# MCU.net
KiCad netlist of a schematic drawn in Altium Designer
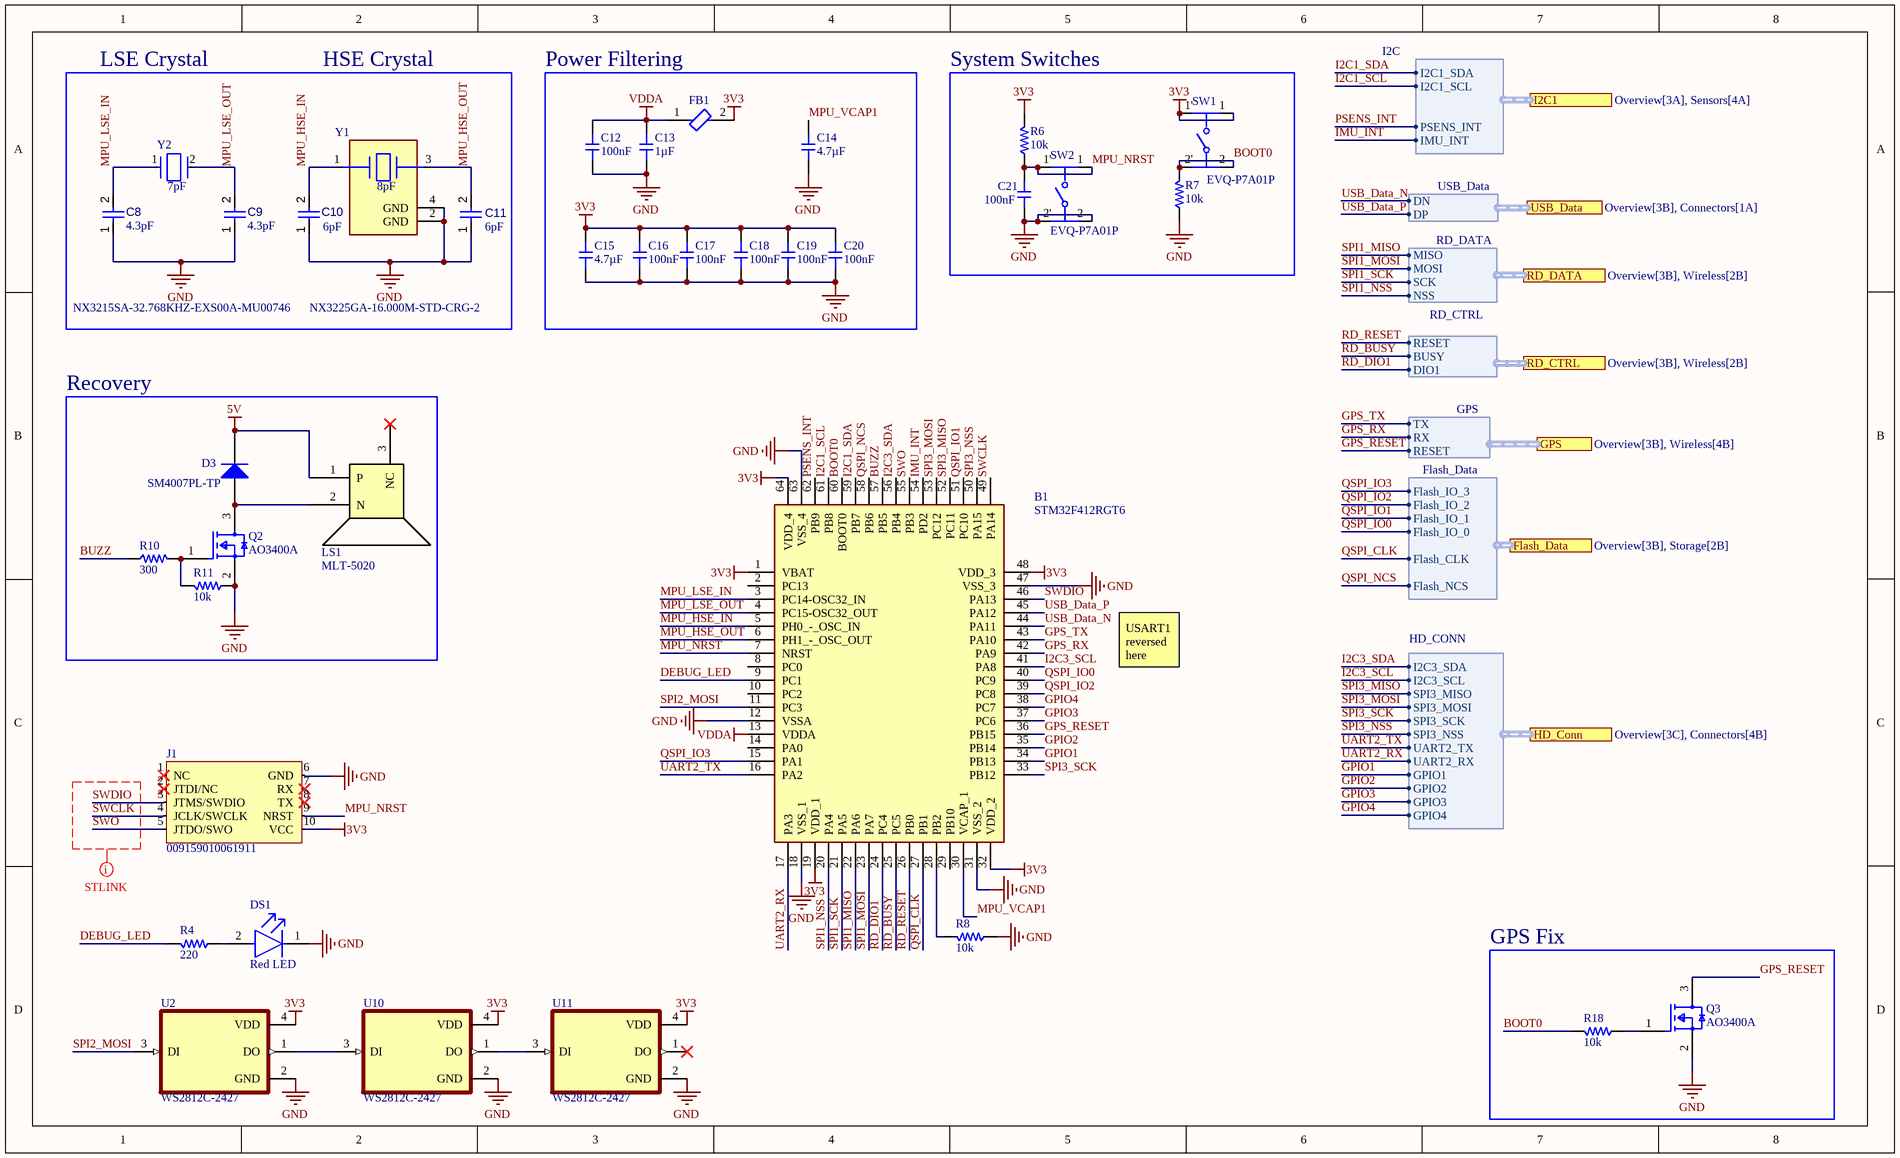
[diagram p0: MCU.SchDoc]

(export (version "E")
  (design (tool "Eeschema 10.0.6"))
  (components
    (comp (ref "B1")
      (value "STM32F412RGT6")
      (footprint "QFP50P1200X1200X160-64N")
      (description "ARM Microcontrollers - MCU 16/32-BITS MICROS")
      (fields
        (field (name "MANUFACTURER") "STMicroelectronics")
        (field (name "MOUSER PART NUMBER") "511-STM32F412RGT6")
      )
      (libsource (lib "StrathSEDS") (part "STM32F412RGT6"))
    )
    (comp (ref "C8")
      (value "4.3pF")
      (footprint "CAP-0402")
      (description "50V 4.3pF NP0 0402  Multilayer Ceramic Capacitors MLCC - SMD/SMT ROHS")
      (fields (field (name "JLCPCB PART NUMBER") "C147367") (field (name "Comment") "C1005NP0439CGTS"))
      (libsource (lib "StrathSEDS") (part "CAP-NP-2"))
    )
    (comp (ref "C9")
      (value "4.3pF")
      (footprint "CAP-0402")
      (description "50V 4.3pF NP0 0402  Multilayer Ceramic Capacitors MLCC - SMD/SMT ROHS")
      (fields (field (name "JLCPCB PART NUMBER") "C147367") (field (name "Comment") "C1005NP0439CGTS"))
      (libsource (lib "StrathSEDS") (part "CAP-NP-2"))
    )
    (comp (ref "C10")
      (value "6pF")
      (footprint "CAP-0402")
      (description "50V 6pF C0G 0402  Multilayer Ceramic Capacitors MLCC - SMD/SMT ROHS")
      (fields (field (name "JLCPCB PART NUMBER") "C1575") (field (name "Comment") "0402CG6R0C500NT"))
      (libsource (lib "StrathSEDS") (part "CAP-NP-2"))
    )
    (comp (ref "C11")
      (value "6pF")
      (footprint "CAP-0402")
      (description "50V 6pF C0G 0402  Multilayer Ceramic Capacitors MLCC - SMD/SMT ROHS")
      (fields (field (name "JLCPCB PART NUMBER") "C1575") (field (name "Comment") "0402CG6R0C500NT"))
      (libsource (lib "StrathSEDS") (part "CAP-NP-2"))
    )
    (comp (ref "C12")
      (value "100nF")
      (footprint "CAP-0402")
      (description "Capacitor, Ceramic (MLCC), 100nF, ±10%, 16V, X7R, ±10%, SMD 0402")
      (fields (field (name "TOLERANCE") "10%") (field (name "JLCPCB BASIC PART") "Yes"))
      (libsource (lib "StrathSEDS") (part "GRM21BR61H106KE43L"))
    )
    (comp (ref "C13")
      (value "1µF")
      (footprint "CAP-0402")
      (description "Capacitor, Ceramic (MLCC), 1uF, ±10%, 25V, X5R, ±10%, SMD 0402")
      (fields (field (name "TOLERANCE") "10%") (field (name "JLCPCB BASIC PART") "Yes"))
      (libsource (lib "StrathSEDS") (part "GRM21BR61H106KE43L"))
    )
    (comp (ref "C14")
      (value "4.7µF")
      (footprint "CAP-0402")
      (description "Capacitor, Ceramic (MLCC), 4.7uF, ±20%, 10V, X5R, ±20%, SMD 0402")
      (fields (field (name "TOLERANCE") "20%") (field (name "MANUFACTURER PART NUMBER") "CL05A475MP5NRNC"))
      (libsource (lib "StrathSEDS") (part "GRM21BR61H106KE43L"))
    )
    (comp (ref "C15")
      (value "4.7µF")
      (footprint "CAP-0402")
      (description "Capacitor, Ceramic (MLCC), 4.7uF, ±20%, 10V, X5R, ±20%, SMD 0402")
      (fields (field (name "TOLERANCE") "20%") (field (name "MANUFACTURER PART NUMBER") "CL05A475MP5NRNC"))
      (libsource (lib "StrathSEDS") (part "GRM21BR61H106KE43L"))
    )
    (comp (ref "C16")
      (value "100nF")
      (footprint "CAP-0402")
      (description "Capacitor, Ceramic (MLCC), 100nF, ±10%, 16V, X7R, ±10%, SMD 0402")
      (fields (field (name "TOLERANCE") "10%") (field (name "JLCPCB BASIC PART") "Yes"))
      (libsource (lib "StrathSEDS") (part "GRM21BR61H106KE43L"))
    )
    (comp (ref "C17")
      (value "100nF")
      (footprint "CAP-0402")
      (description "Capacitor, Ceramic (MLCC), 100nF, ±10%, 16V, X7R, ±10%, SMD 0402")
      (fields (field (name "TOLERANCE") "10%") (field (name "JLCPCB BASIC PART") "Yes"))
      (libsource (lib "StrathSEDS") (part "GRM21BR61H106KE43L"))
    )
    (comp (ref "C18")
      (value "100nF")
      (footprint "CAP-0402")
      (description "Capacitor, Ceramic (MLCC), 100nF, ±10%, 16V, X7R, ±10%, SMD 0402")
      (fields (field (name "TOLERANCE") "10%") (field (name "JLCPCB BASIC PART") "Yes"))
      (libsource (lib "StrathSEDS") (part "GRM21BR61H106KE43L"))
    )
    (comp (ref "C19")
      (value "100nF")
      (footprint "CAP-0402")
      (description "Capacitor, Ceramic (MLCC), 100nF, ±10%, 16V, X7R, ±10%, SMD 0402")
      (fields (field (name "TOLERANCE") "10%") (field (name "JLCPCB BASIC PART") "Yes"))
      (libsource (lib "StrathSEDS") (part "GRM21BR61H106KE43L"))
    )
    (comp (ref "C20")
      (value "100nF")
      (footprint "CAP-0402")
      (description "Capacitor, Ceramic (MLCC), 100nF, ±10%, 16V, X7R, ±10%, SMD 0402")
      (fields (field (name "TOLERANCE") "10%") (field (name "JLCPCB BASIC PART") "Yes"))
      (libsource (lib "StrathSEDS") (part "GRM21BR61H106KE43L"))
    )
    (comp (ref "C21")
      (value "100nF")
      (footprint "CAP-0402")
      (description "Capacitor, Ceramic (MLCC), 100nF, ±10%, 16V, X7R, ±10%, SMD 0402")
      (fields (field (name "TOLERANCE") "10%") (field (name "JLCPCB BASIC PART") "Yes"))
      (libsource (lib "StrathSEDS") (part "GRM21BR61H106KE43L"))
    )
    (comp (ref "D3")
      (value "SM4007PL-TP")
      (footprint "MCC-SOD-123FL_V")
      (description "DIODE GEN PURP 1KV 1A SOD123FL")
      (fields (field (name "LCSC PART #") "C64898"))
      (libsource (lib "StrathSEDS") (part "D-AK-2"))
    )
    (comp (ref "DS1")
      (value "Red LED")
      (footprint "FP-LTST-C190GKT-MFG")
      (description "SZYY0603R")
      (fields (field (name "JLCPCB PART NUMBER") "C2286"))
      (libsource (lib "StrathSEDS Mach 22") (part "8706943c75ba83719d021d2fdc84c58"))
    )
    (comp (ref "FB1")
      (value "BLM15AG601SN1D")
      (footprint "FP-BLM15-0_05-IPC_A")
      (description "520mΩ ±25% 600Ω@100MHz 0402  Ferrite Beads ROHS")
      (fields (field (name "JLCPCB PART NUMBER") "C76884"))
      (libsource (lib "StrathSEDS") (part "5f30dd21d616792df468990f7003faa"))
    )
    (comp (ref "J1")
      (value "009159010061911")
      (footprint "009159010061911-Footprint-1")
      (description "AVX edge to edge connector 10pin")
      (libsource (lib "StrathSEDS") (part "009159010061911"))
    )
    (comp (ref "LS1")
      (value "MLT-5020")
      (footprint "MLT-5020")
      (description "Externally Driven Magnetic 4000Hz SMD,5x5mm  Buzzers ROHS")
      (fields (field (name "JLCPCB PART NUMBER") "C94598"))
      (libsource (lib "StrathSEDS") (part "MLT-5020"))
    )
    (comp (ref "Q2")
      (value "AO3400A")
      (footprint "FP-SOT23-IPC_C")
      (description "N沟道 VDS=30V VGS=±12V ID=5.7A P=1.4W")
      (fields (field (name "LCSC PART #") "C20917"))
      (libsource (lib "StrathSEDS") (part "0a9ea7c96deaaede766a5b531c28de0"))
    )
    (comp (ref "Q3")
      (value "AO3400A")
      (footprint "FP-SOT23-IPC_C")
      (description "N沟道 VDS=30V VGS=±12V ID=5.7A P=1.4W")
      (fields (field (name "JLCPCB PART NUMBER") "C20917"))
      (libsource (lib "StrathSEDS") (part "0a9ea7c96deaaede766a5b531c28de0"))
    )
    (comp (ref "R4")
      (value "220")
      (footprint "RES-0402")
      (description "Resistor, 220Ω, ±1%, 62.5mW, 50V, ±100ppm/℃, -55℃~+155℃, SMD 0402")
      (fields (field (name "MANUFACTURER") "Uniroyal") (field (name "TOLERANCE") "1%"))
      (libsource (lib "StrathSEDS") (part "1206W4F7500T5E"))
    )
    (comp (ref "R6")
      (value "10k")
      (footprint "RES-0402")
      (description "Resistor, 10kΩ, ±1%, 62.5mW, 50V, ±100ppm/℃, -55℃~+155℃, SMD 0402")
      (fields (field (name "TOLERANCE") "1%") (field (name "JLCPCB PART NUMBER") "C25744"))
      (libsource (lib "StrathSEDS") (part "1206W4F7500T5E"))
    )
    (comp (ref "R7")
      (value "10k")
      (footprint "RES-0402")
      (description "Resistor, 10kΩ, ±1%, 62.5mW, 50V, ±100ppm/℃, -55℃~+155℃, SMD 0402")
      (fields (field (name "TOLERANCE") "1%") (field (name "JLCPCB PART NUMBER") "C25744"))
      (libsource (lib "StrathSEDS") (part "1206W4F7500T5E"))
    )
    (comp (ref "R8")
      (value "10k")
      (footprint "RES-0402")
      (description "Resistor, 10kΩ, ±1%, 62.5mW, 50V, ±100ppm/℃, -55℃~+155℃, SMD 0402")
      (fields (field (name "TOLERANCE") "1%") (field (name "JLCPCB PART NUMBER") "C25744"))
      (libsource (lib "StrathSEDS") (part "1206W4F7500T5E"))
    )
    (comp (ref "R10")
      (value "300")
      (footprint "RES-0402")
      (description "Resistor, 300Ω, ±1%, 62.5mW, 50V, ±100ppm/℃, -55℃~+155℃, SMD 0402")
      (fields
        (field (name "JLCPCB PART NUMBER") "C25102")
        (field (name "MANUFACTURER PART NUMBER") "0402WGF3000TCE")
      )
      (libsource (lib "StrathSEDS") (part "1206W4F7500T5E"))
    )
    (comp (ref "R11")
      (value "10k")
      (footprint "RES-0402")
      (description "Resistor, 10kΩ, ±1%, 62.5mW, 50V, ±100ppm/℃, -55℃~+155℃, SMD 0402")
      (fields (field (name "TOLERANCE") "1%") (field (name "JLCPCB PART NUMBER") "C25744"))
      (libsource (lib "StrathSEDS") (part "1206W4F7500T5E"))
    )
    (comp (ref "R18")
      (value "10k")
      (footprint "RES-0402")
      (description "Resistor, 10kΩ, ±1%, 62.5mW, 50V, ±100ppm/℃, -55℃~+155℃, SMD 0402")
      (fields (field (name "TOLERANCE") "1%") (field (name "JLCPCB PART NUMBER") "C25744"))
      (libsource (lib "StrathSEDS") (part "1206W4F7500T5E"))
    )
    (comp (ref "SW1")
      (value "EVQ-P7A01P")
      (footprint "FP-EVQ-P7A01P-MFG")
      (description "Switch Tactile N.O. SPST Rectangular Button Gull Wing 0.05A 12VDC 2.2N SMD Embossed T/R")
      (fields (field (name "JLCPCB PART NUMBER") "C79167"))
      (libsource (lib "StrathSEDS") (part "c93661f14280f1e5a1fd29b4a471f7d"))
    )
    (comp (ref "SW2")
      (value "EVQ-P7A01P")
      (footprint "FP-EVQ-P7A01P-MFG")
      (description "Switch Tactile N.O. SPST Rectangular Button Gull Wing 0.05A 12VDC 2.2N SMD Embossed T/R")
      (fields (field (name "JLCPCB PART NUMBER") "C79167"))
      (libsource (lib "StrathSEDS") (part "c93661f14280f1e5a1fd29b4a471f7d"))
    )
    (comp (ref "U2")
      (value "WS2812C-2427")
      (footprint "WS2812C-2427-Footprint-1")
      (description "SMD,2.4x2.7mm  Light Emitting Diodes (LED) ROHS")
      (fields (field (name "JLCPCB PART NUMBER") "C4154872"))
      (libsource (lib "StrathSEDS") (part "WS2812C-2427"))
    )
    (comp (ref "U10")
      (value "WS2812C-2427")
      (footprint "WS2812C-2427-Footprint-1")
      (description "SMD,2.4x2.7mm  Light Emitting Diodes (LED) ROHS")
      (fields (field (name "JLCPCB PART NUMBER") "C4154872"))
      (libsource (lib "StrathSEDS") (part "WS2812C-2427"))
    )
    (comp (ref "U11")
      (value "WS2812C-2427")
      (footprint "WS2812C-2427-Footprint-1")
      (description "SMD,2.4x2.7mm  Light Emitting Diodes (LED) ROHS")
      (fields (field (name "JLCPCB PART NUMBER") "C4154872"))
      (libsource (lib "StrathSEDS") (part "WS2812C-2427"))
    )
    (comp (ref "Y1")
      (value "NX3225GA-16.000M-STD-CRG-2")
      (footprint "FP-NX3225GA-MFG")
      (description "Crystal 16MHz ±20ppm (Tol) ±30ppm (Stability) 8pF FUND 80Ohm Automotive 4-Pin SMD")
      (fields (field (name "JLCPCB PART NUMBER") "C156247") (field (name "ALTIUM_VALUE") "8pF"))
      (libsource (lib "StrathSEDS Mach 22") (part "6320effb7d3e443b36bf79d8ebe02e5"))
    )
    (comp (ref "Y2")
      (value "NX3215SA-32.768KHZ-EXS00A-MU00746")
      (footprint "FP-NX3215SA-MFG")
      (description "Crystal 32.7680KHZ 7PF SMD")
      (fields (field (name "JLCPCB PART NUMBER") "C5136773") (field (name "ALTIUM_VALUE") "7pF"))
      (libsource (lib "StrathSEDS Mach 22") (part "c23a69dc6c9e2f18f2079038eb95dd1"))
    )
  )
  (nets
    (net (code "8") (name "/BOOT0") (class "Default")
      (node (ref "B1") (pin "60") (pinfunction "BOOT0_60") (pintype "passive"))
      (node (ref "R18") (pin "2") (pinfunction "2_2") (pintype "passive"))
      (node (ref "R7") (pin "2") (pinfunction "2_2") (pintype "passive"))
      (node (ref "SW1") (pin "2") (pinfunction "2_2") (pintype "passive"))
      (node (ref "SW1") (pin "2'") (pinfunction "2'_2'") (pintype "passive"))
    )
    (net (code "9") (name "/BUZZ") (class "Default")
      (node (ref "B1") (pin "57") (pinfunction "PB5_57") (pintype "passive"))
      (node (ref "R10") (pin "1") (pinfunction "1_1") (pintype "passive"))
    )
    (net (code "10") (name "/DEBUG_LED") (class "Default")
      (node (ref "B1") (pin "9") (pinfunction "PC1_9") (pintype "passive"))
      (node (ref "R4") (pin "2") (pinfunction "2_2") (pintype "passive"))
    )
    (net (code "11") (name "/GPIO1") (class "Default")
      (node (ref "B1") (pin "34") (pinfunction "PB13_34") (pintype "passive"))
    )
    (net (code "12") (name "/GPIO2") (class "Default")
      (node (ref "B1") (pin "35") (pinfunction "PB14_35") (pintype "passive"))
    )
    (net (code "13") (name "/GPIO3") (class "Default")
      (node (ref "B1") (pin "37") (pinfunction "PC6_37") (pintype "passive"))
    )
    (net (code "14") (name "/GPIO4") (class "Default")
      (node (ref "B1") (pin "38") (pinfunction "PC7_38") (pintype "passive"))
    )
    (net (code "15") (name "/GPS_RESET") (class "Default")
      (node (ref "B1") (pin "36") (pinfunction "PB15_36") (pintype "passive"))
      (node (ref "Q3") (pin "3") (pinfunction "D_3") (pintype "passive"))
    )
    (net (code "16") (name "/GPS_RX") (class "Default")
      (node (ref "B1") (pin "42") (pinfunction "PA9_42") (pintype "passive"))
    )
    (net (code "17") (name "/GPS_TX") (class "Default")
      (node (ref "B1") (pin "43") (pinfunction "PA10_43") (pintype "passive"))
    )
    (net (code "18") (name "/I2C1_SCL") (class "Default")
      (node (ref "B1") (pin "61") (pinfunction "PB8_61") (pintype "passive"))
    )
    (net (code "19") (name "/I2C1_SDA") (class "Default")
      (node (ref "B1") (pin "59") (pinfunction "PB7_59") (pintype "passive"))
    )
    (net (code "20") (name "/I2C3_SCL") (class "Default")
      (node (ref "B1") (pin "41") (pinfunction "PA8_41") (pintype "passive"))
    )
    (net (code "21") (name "/I2C3_SDA") (class "Default")
      (node (ref "B1") (pin "56") (pinfunction "PB4_56") (pintype "passive"))
    )
    (net (code "22") (name "/IMU_INT") (class "Default")
      (node (ref "B1") (pin "54") (pinfunction "PD2_54") (pintype "passive"))
    )
    (net (code "23") (name "/MPU_HSE_IN") (class "Default")
      (node (ref "B1") (pin "5") (pinfunction "PH0_-_OSC_IN_5") (pintype "passive"))
      (node (ref "C10") (pin "2") (pinfunction "2_2") (pintype "passive"))
      (node (ref "Y1") (pin "1") (pinfunction "1_1") (pintype "passive"))
    )
    (net (code "24") (name "/MPU_HSE_OUT") (class "Default")
      (node (ref "B1") (pin "6") (pinfunction "PH1_-_OSC_OUT_6") (pintype "passive"))
      (node (ref "C11") (pin "2") (pinfunction "2_2") (pintype "passive"))
      (node (ref "Y1") (pin "3") (pinfunction "3_3") (pintype "passive"))
    )
    (net (code "25") (name "/MPU_LSE_IN") (class "Default")
      (node (ref "B1") (pin "3") (pinfunction "PC14-OSC32_IN_3") (pintype "passive"))
      (node (ref "C8") (pin "2") (pinfunction "2_2") (pintype "passive"))
      (node (ref "Y2") (pin "1") (pinfunction "1_1") (pintype "passive"))
    )
    (net (code "26") (name "/MPU_LSE_OUT") (class "Default")
      (node (ref "B1") (pin "4") (pinfunction "PC15-OSC32_OUT_4") (pintype "passive"))
      (node (ref "C9") (pin "2") (pinfunction "2_2") (pintype "passive"))
      (node (ref "Y2") (pin "2") (pinfunction "2_2") (pintype "passive"))
    )
    (net (code "27") (name "/MPU_NRST") (class "Default")
      (node (ref "B1") (pin "7") (pinfunction "NRST_7") (pintype "passive"))
      (node (ref "C21") (pin "2") (pinfunction "2_2") (pintype "passive"))
      (node (ref "J1") (pin "9") (pinfunction "NRST_9") (pintype "output"))
      (node (ref "R6") (pin "1") (pinfunction "1_1") (pintype "passive"))
      (node (ref "SW2") (pin "1") (pinfunction "1_1") (pintype "passive"))
      (node (ref "SW2") (pin "1'") (pinfunction "1'_1'") (pintype "passive"))
    )
    (net (code "28") (name "/MPU_VCAP1") (class "Default")
      (node (ref "B1") (pin "30") (pinfunction "VCAP_1_30") (pintype "power_in"))
      (node (ref "C14") (pin "2") (pinfunction "2_2") (pintype "passive"))
    )
    (net (code "29") (name "/PSENS_INT") (class "Default")
      (node (ref "B1") (pin "62") (pinfunction "PB9_62") (pintype "passive"))
    )
    (net (code "30") (name "/QSPI_CLK") (class "Default")
      (node (ref "B1") (pin "27") (pinfunction "PB1_27") (pintype "passive"))
    )
    (net (code "31") (name "/QSPI_IO0") (class "Default")
      (node (ref "B1") (pin "40") (pinfunction "PC9_40") (pintype "passive"))
    )
    (net (code "32") (name "/QSPI_IO1") (class "Default")
      (node (ref "B1") (pin "51") (pinfunction "PC10_51") (pintype "passive"))
    )
    (net (code "33") (name "/QSPI_IO2") (class "Default")
      (node (ref "B1") (pin "39") (pinfunction "PC8_39") (pintype "passive"))
    )
    (net (code "34") (name "/QSPI_IO3") (class "Default")
      (node (ref "B1") (pin "15") (pinfunction "PA1_15") (pintype "passive"))
    )
    (net (code "35") (name "/QSPI_NCS") (class "Default")
      (node (ref "B1") (pin "58") (pinfunction "PB6_58") (pintype "passive"))
    )
    (net (code "36") (name "/RD_BUSY") (class "Default")
      (node (ref "B1") (pin "25") (pinfunction "PC5_25") (pintype "passive"))
    )
    (net (code "37") (name "/RD_DIO1") (class "Default")
      (node (ref "B1") (pin "24") (pinfunction "PC4_24") (pintype "passive"))
    )
    (net (code "38") (name "/RD_RESET") (class "Default")
      (node (ref "B1") (pin "26") (pinfunction "PB0_26") (pintype "passive"))
    )
    (net (code "39") (name "/SPI1_MISO") (class "Default")
      (node (ref "B1") (pin "22") (pinfunction "PA6_22") (pintype "passive"))
    )
    (net (code "40") (name "/SPI1_MOSI") (class "Default")
      (node (ref "B1") (pin "23") (pinfunction "PA7_23") (pintype "passive"))
    )
    (net (code "41") (name "/SPI1_NSS") (class "Default")
      (node (ref "B1") (pin "20") (pinfunction "PA4_20") (pintype "passive"))
    )
    (net (code "42") (name "/SPI1_SCK") (class "Default")
      (node (ref "B1") (pin "21") (pinfunction "PA5_21") (pintype "passive"))
    )
    (net (code "43") (name "/SPI2_MOSI") (class "Default")
      (node (ref "B1") (pin "11") (pinfunction "PC3_11") (pintype "passive"))
      (node (ref "U2") (pin "3") (pinfunction "DI_3") (pintype "input"))
    )
    (net (code "44") (name "/SPI3_MISO") (class "Default")
      (node (ref "B1") (pin "52") (pinfunction "PC11_52") (pintype "passive"))
    )
    (net (code "45") (name "/SPI3_MOSI") (class "Default")
      (node (ref "B1") (pin "53") (pinfunction "PC12_53") (pintype "passive"))
    )
    (net (code "46") (name "/SPI3_NSS") (class "Default")
      (node (ref "B1") (pin "50") (pinfunction "PA15_50") (pintype "passive"))
    )
    (net (code "47") (name "/SPI3_SCK") (class "Default")
      (node (ref "B1") (pin "33") (pinfunction "PB12_33") (pintype "passive"))
    )
    (net (code "48") (name "/SWCLK") (class "Default")
      (node (ref "B1") (pin "49") (pinfunction "PA14_49") (pintype "passive"))
      (node (ref "J1") (pin "4") (pinfunction "JCLK/SWCLK_4") (pintype "output"))
    )
    (net (code "49") (name "/SWDIO") (class "Default")
      (node (ref "B1") (pin "46") (pinfunction "PA13_46") (pintype "passive"))
      (node (ref "J1") (pin "3") (pinfunction "JTMS/SWDIO_3") (pintype "bidirectional"))
    )
    (net (code "50") (name "/SWO") (class "Default")
      (node (ref "B1") (pin "55") (pinfunction "PB3_55") (pintype "passive"))
      (node (ref "J1") (pin "5") (pinfunction "JTDO/SWO_5") (pintype "input"))
    )
    (net (code "51") (name "/UART2_RX") (class "Default")
      (node (ref "B1") (pin "17") (pinfunction "PA3_17") (pintype "passive"))
    )
    (net (code "52") (name "/UART2_TX") (class "Default")
      (node (ref "B1") (pin "16") (pinfunction "PA2_16") (pintype "passive"))
    )
    (net (code "53") (name "/USB_Data_N") (class "Default")
      (node (ref "B1") (pin "44") (pinfunction "PA11_44") (pintype "passive"))
    )
    (net (code "54") (name "/USB_Data_P") (class "Default")
      (node (ref "B1") (pin "45") (pinfunction "PA12_45") (pintype "passive"))
    )
    (net (code "62") (name "3V3") (class "Default")
      (node (ref "B1") (pin "1") (pinfunction "VBAT_1") (pintype "power_in"))
      (node (ref "B1") (pin "19") (pinfunction "VDD_1_19") (pintype "power_in"))
      (node (ref "B1") (pin "32") (pinfunction "VDD_2_32") (pintype "power_in"))
      (node (ref "B1") (pin "48") (pinfunction "VDD_3_48") (pintype "power_in"))
      (node (ref "B1") (pin "64") (pinfunction "VDD_4_64") (pintype "power_in"))
      (node (ref "C15") (pin "2") (pinfunction "2_2") (pintype "passive"))
      (node (ref "C16") (pin "2") (pinfunction "2_2") (pintype "passive"))
      (node (ref "C17") (pin "2") (pinfunction "2_2") (pintype "passive"))
      (node (ref "C18") (pin "2") (pinfunction "2_2") (pintype "passive"))
      (node (ref "C19") (pin "2") (pinfunction "2_2") (pintype "passive"))
      (node (ref "C20") (pin "2") (pinfunction "2_2") (pintype "passive"))
      (node (ref "FB1") (pin "2") (pinfunction "2_2") (pintype "passive"))
      (node (ref "J1") (pin "10") (pinfunction "VCC_10") (pintype "power_in"))
      (node (ref "R6") (pin "2") (pinfunction "2_2") (pintype "passive"))
      (node (ref "SW1") (pin "1") (pinfunction "1_1") (pintype "passive"))
      (node (ref "SW1") (pin "1'") (pinfunction "1'_1'") (pintype "passive"))
      (node (ref "U10") (pin "4") (pinfunction "VDD_4") (pintype "power_in"))
      (node (ref "U11") (pin "4") (pinfunction "VDD_4") (pintype "power_in"))
      (node (ref "U2") (pin "4") (pinfunction "VDD_4") (pintype "power_in"))
    )
    (net (code "63") (name "5V") (class "Default")
      (node (ref "D3") (pin "2") (pinfunction "K_2") (pintype "passive"))
      (node (ref "LS1") (pin "1") (pinfunction "P_1") (pintype "power_in"))
    )
    (net (code "64") (name "GND") (class "Default")
      (node (ref "B1") (pin "12") (pinfunction "VSSA_12") (pintype "power_in"))
      (node (ref "B1") (pin "18") (pinfunction "VSS_1_18") (pintype "power_in"))
      (node (ref "B1") (pin "31") (pinfunction "VSS_2_31") (pintype "power_in"))
      (node (ref "B1") (pin "47") (pinfunction "VSS_3_47") (pintype "power_in"))
      (node (ref "B1") (pin "63") (pinfunction "VSS_4_63") (pintype "power_in"))
      (node (ref "C10") (pin "1") (pinfunction "1_1") (pintype "passive"))
      (node (ref "C11") (pin "1") (pinfunction "1_1") (pintype "passive"))
      (node (ref "C12") (pin "1") (pinfunction "1_1") (pintype "passive"))
      (node (ref "C13") (pin "1") (pinfunction "1_1") (pintype "passive"))
      (node (ref "C14") (pin "1") (pinfunction "1_1") (pintype "passive"))
      (node (ref "C15") (pin "1") (pinfunction "1_1") (pintype "passive"))
      (node (ref "C16") (pin "1") (pinfunction "1_1") (pintype "passive"))
      (node (ref "C17") (pin "1") (pinfunction "1_1") (pintype "passive"))
      (node (ref "C18") (pin "1") (pinfunction "1_1") (pintype "passive"))
      (node (ref "C19") (pin "1") (pinfunction "1_1") (pintype "passive"))
      (node (ref "C20") (pin "1") (pinfunction "1_1") (pintype "passive"))
      (node (ref "C21") (pin "1") (pinfunction "1_1") (pintype "passive"))
      (node (ref "C8") (pin "1") (pinfunction "1_1") (pintype "passive"))
      (node (ref "C9") (pin "1") (pinfunction "1_1") (pintype "passive"))
      (node (ref "DS1") (pin "1") (pinfunction "C_1") (pintype "passive"))
      (node (ref "J1") (pin "6") (pinfunction "GND_6") (pintype "power_in"))
      (node (ref "Q2") (pin "2") (pinfunction "S_2") (pintype "passive"))
      (node (ref "Q3") (pin "2") (pinfunction "S_2") (pintype "passive"))
      (node (ref "R11") (pin "1") (pinfunction "1_1") (pintype "passive"))
      (node (ref "R7") (pin "1") (pinfunction "1_1") (pintype "passive"))
      (node (ref "R8") (pin "1") (pinfunction "1_1") (pintype "passive"))
      (node (ref "SW2") (pin "2") (pinfunction "2_2") (pintype "passive"))
      (node (ref "SW2") (pin "2'") (pinfunction "2'_2'") (pintype "passive"))
      (node (ref "U10") (pin "2") (pinfunction "GND_2") (pintype "power_in"))
      (node (ref "U11") (pin "2") (pinfunction "GND_2") (pintype "power_in"))
      (node (ref "U2") (pin "2") (pinfunction "GND_2") (pintype "power_in"))
      (node (ref "Y1") (pin "2") (pinfunction "GND_2") (pintype "power_in"))
      (node (ref "Y1") (pin "4") (pinfunction "GND_4") (pintype "power_in"))
    )
    (net (code "65") (name "Net-(B1-PB2)") (class "Default")
      (node (ref "B1") (pin "28") (pinfunction "PB2_28") (pintype "passive"))
      (node (ref "R8") (pin "2") (pinfunction "2_2") (pintype "passive"))
    )
    (net (code "66") (name "Net-(D3-A)") (class "Default")
      (node (ref "D3") (pin "1") (pinfunction "A_1") (pintype "passive"))
      (node (ref "LS1") (pin "2") (pinfunction "N_2") (pintype "power_in"))
      (node (ref "Q2") (pin "3") (pinfunction "D_3") (pintype "passive"))
    )
    (net (code "67") (name "Net-(DS1-A)") (class "Default")
      (node (ref "DS1") (pin "2") (pinfunction "A_2") (pintype "passive"))
      (node (ref "R4") (pin "1") (pinfunction "1_1") (pintype "passive"))
    )
    (net (code "68") (name "Net-(Q2-G)") (class "Default")
      (node (ref "Q2") (pin "1") (pinfunction "G_1") (pintype "passive"))
      (node (ref "R10") (pin "2") (pinfunction "2_2") (pintype "passive"))
      (node (ref "R11") (pin "2") (pinfunction "2_2") (pintype "passive"))
    )
    (net (code "69") (name "Net-(Q3-G)") (class "Default")
      (node (ref "Q3") (pin "1") (pinfunction "G_1") (pintype "passive"))
      (node (ref "R18") (pin "1") (pinfunction "1_1") (pintype "passive"))
    )
    (net (code "70") (name "Net-(U10-DI)") (class "Default")
      (node (ref "U10") (pin "3") (pinfunction "DI_3") (pintype "input"))
      (node (ref "U2") (pin "1") (pinfunction "DO_1") (pintype "output"))
    )
    (net (code "71") (name "Net-(U10-DO)") (class "Default")
      (node (ref "U10") (pin "1") (pinfunction "DO_1") (pintype "output"))
      (node (ref "U11") (pin "3") (pinfunction "DI_3") (pintype "input"))
    )
    (net (code "72") (name "VDDA") (class "Default")
      (node (ref "B1") (pin "13") (pinfunction "VDDA_13") (pintype "power_in"))
      (node (ref "C12") (pin "2") (pinfunction "2_2") (pintype "passive"))
      (node (ref "C13") (pin "2") (pinfunction "2_2") (pintype "passive"))
      (node (ref "FB1") (pin "1") (pinfunction "1_1") (pintype "passive"))
    )
    (net (code "73") (name "unconnected-(B1-PA0-Pad14)") (class "Default")
      (node (ref "B1") (pin "14") (pinfunction "PA0_14") (pintype "passive"))
    )
    (net (code "74") (name "unconnected-(B1-PB10-Pad29)") (class "Default")
      (node (ref "B1") (pin "29") (pinfunction "PB10_29") (pintype "passive"))
    )
    (net (code "75") (name "unconnected-(B1-PC0-Pad8)") (class "Default")
      (node (ref "B1") (pin "8") (pinfunction "PC0_8") (pintype "passive"))
    )
    (net (code "76") (name "unconnected-(B1-PC2-Pad10)") (class "Default")
      (node (ref "B1") (pin "10") (pinfunction "PC2_10") (pintype "passive"))
    )
    (net (code "77") (name "unconnected-(B1-PC13-Pad2)") (class "Default")
      (node (ref "B1") (pin "2") (pinfunction "PC13_2") (pintype "passive"))
    )
    (net (code "78") (name "unconnected-(J1-JTDI{slash}NC-Pad2)") (class "Default")
      (node (ref "J1") (pin "2") (pinfunction "JTDI/NC_2") (pintype "output+no_connect"))
    )
    (net (code "79") (name "unconnected-(J1-NC-Pad1)") (class "Default")
      (node (ref "J1") (pin "1") (pinfunction "NC_1") (pintype "passive+no_connect"))
    )
    (net (code "80") (name "unconnected-(J1-RX-Pad7)") (class "Default")
      (node (ref "J1") (pin "7") (pinfunction "RX_7") (pintype "output+no_connect"))
    )
    (net (code "81") (name "unconnected-(J1-TX-Pad8)") (class "Default")
      (node (ref "J1") (pin "8") (pinfunction "TX_8") (pintype "input+no_connect"))
    )
    (net (code "82") (name "unconnected-(LS1-NC-Pad3)") (class "Default")
      (node (ref "LS1") (pin "3") (pinfunction "NC_3") (pintype "passive+no_connect"))
    )
    (net (code "83") (name "unconnected-(U11-DO-Pad1)") (class "Default")
      (node (ref "U11") (pin "1") (pinfunction "DO_1") (pintype "output+no_connect"))
    )
  )
)
